# msp_talking_tom_v5.net
KiCad netlist of a schematic drawn in EAGLE
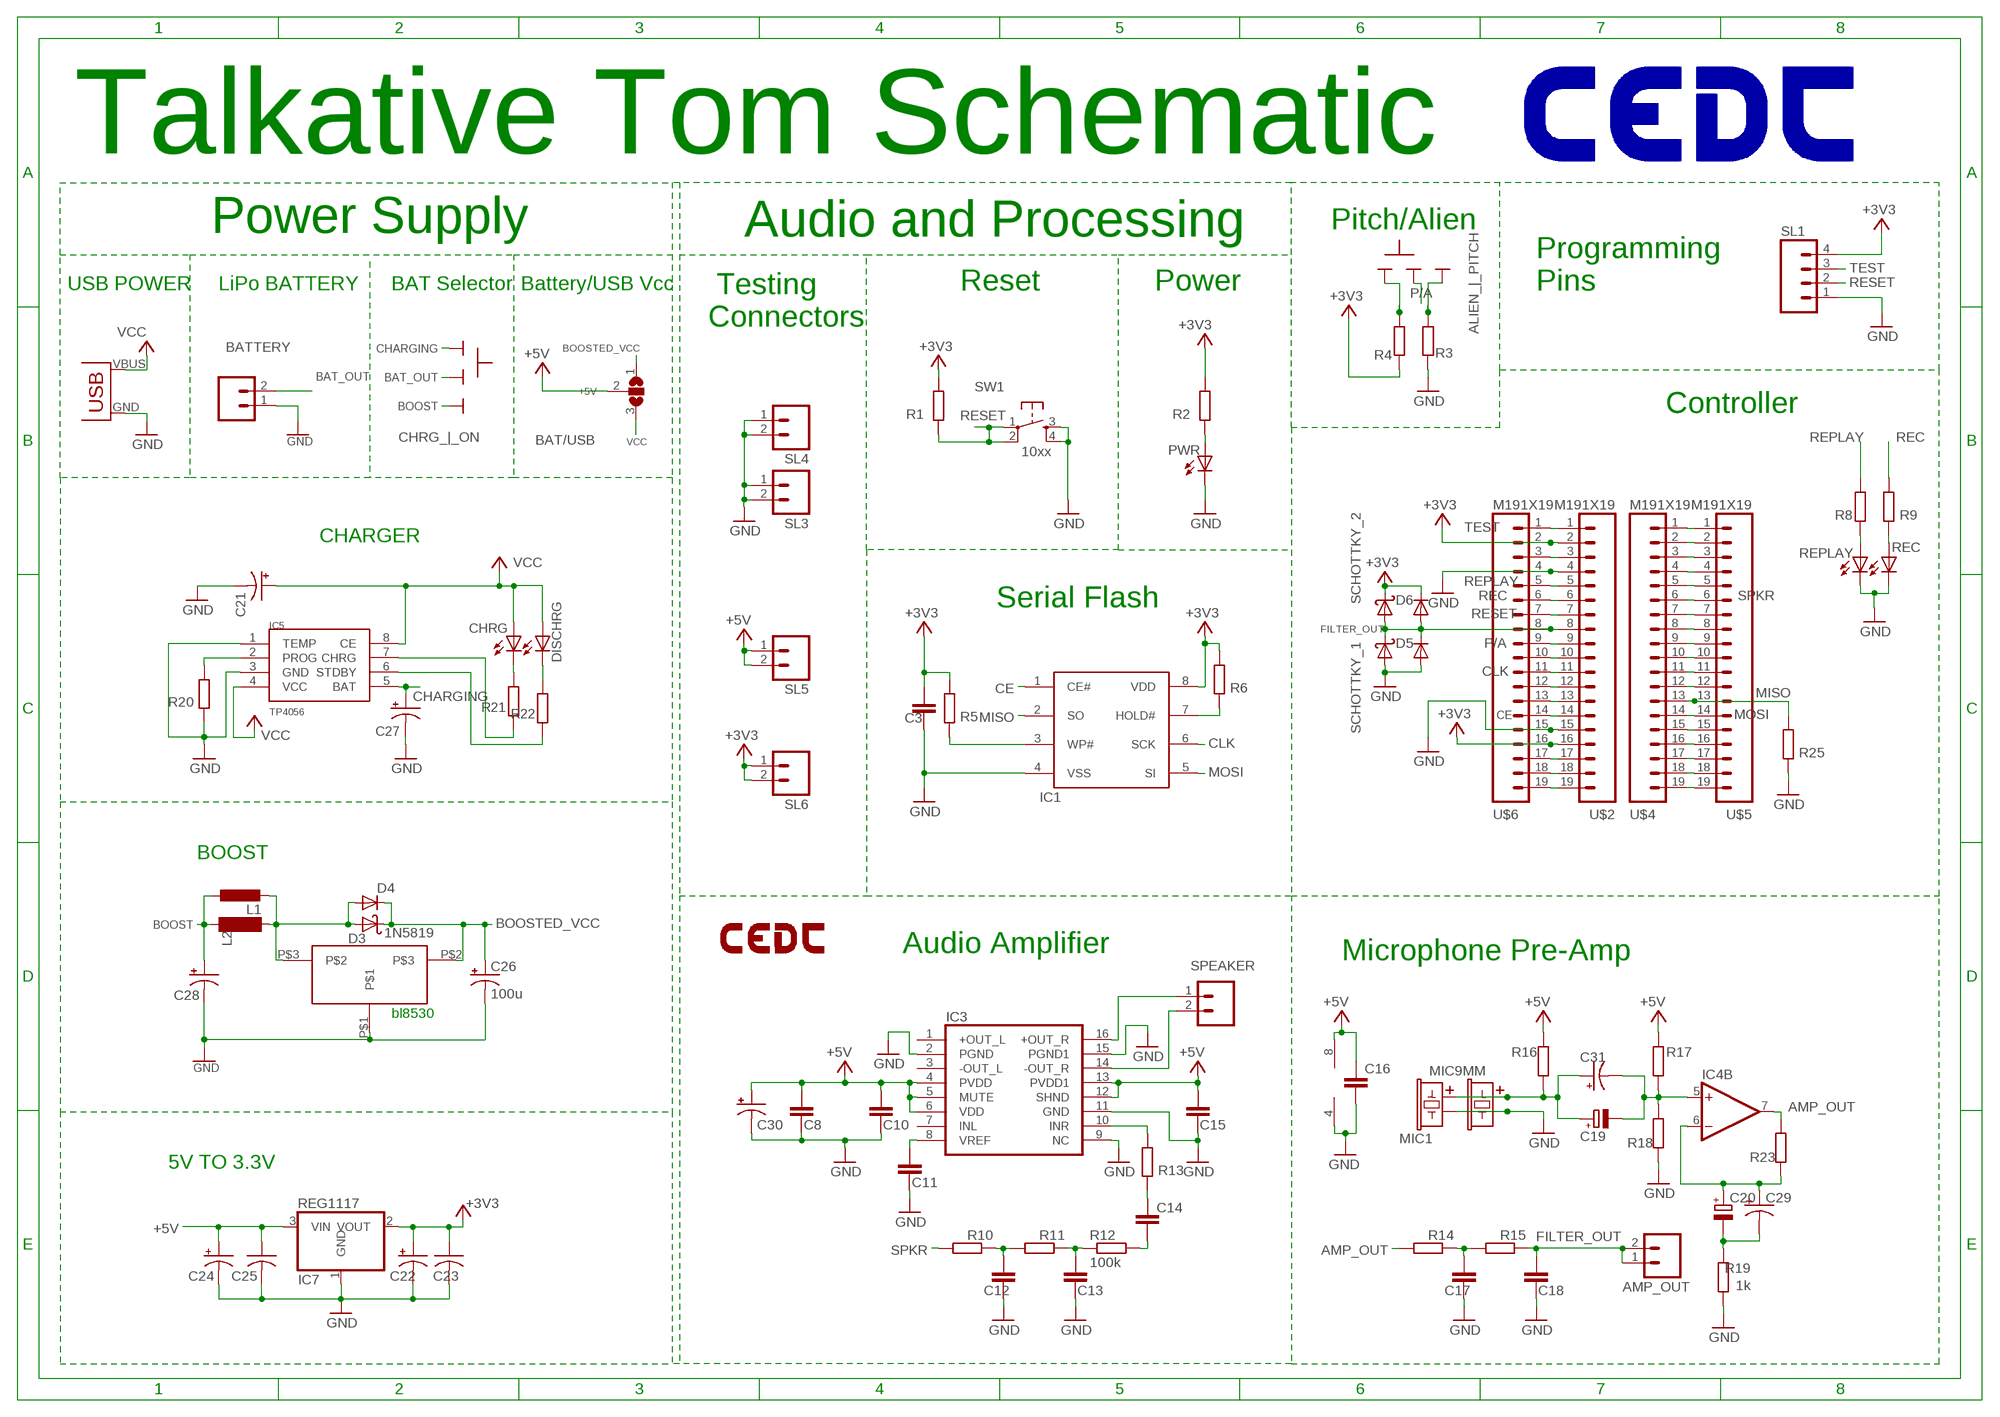
[diagram p0: schematic, sheet 1]

(export (version "E")
  (design (tool "Eeschema 10.0.6"))
  (components
    (comp (ref "ALIEN_|_PITCH")
      (value "SLIDESWITCH-BIG")
      (footprint "eagle-import:BIGSWITCH")
      (libsource (lib "eagle-import") (part "SLIDESWITCH-BIG"))
    )
    (comp (ref "AMP_OUT")
      (value "M02")
      (footprint "eagle-import:02P")
      (libsource (lib "eagle-import") (part "M02"))
    )
    (comp (ref "BAT/USB")
      (value "SJ2W")
      (footprint "eagle-import:SJ_2")
      (libsource (lib "eagle-import") (part "SJ2W"))
    )
    (comp (ref "BATTERY")
      (value "M02JST-PTH-2")
      (footprint "eagle-import:02P")
      (libsource (lib "eagle-import") (part "M02"))
    )
    (comp (ref "C3")
      (value "0.1u")
      (footprint "eagle-import:C0805")
      (libsource (lib "eagle-import") (part "rcl_C-EUC0805"))
    )
    (comp (ref "C8")
      (value "1uf")
      (footprint "eagle-import:C1206")
      (libsource (lib "eagle-import") (part "rcl_C-EUC1206"))
    )
    (comp (ref "C10")
      (value "1uf")
      (footprint "eagle-import:C1206")
      (libsource (lib "eagle-import") (part "rcl_C-EUC1206"))
    )
    (comp (ref "C11")
      (value "0.1uf")
      (footprint "eagle-import:C1206")
      (libsource (lib "eagle-import") (part "rcl_C-EUC1206"))
    )
    (comp (ref "C12")
      (value "0.1u")
      (footprint "eagle-import:C0805")
      (libsource (lib "eagle-import") (part "C-EUC0805"))
    )
    (comp (ref "C13")
      (value "0.1uf")
      (footprint "eagle-import:C0805")
      (libsource (lib "eagle-import") (part "C-EUC0805"))
    )
    (comp (ref "C14")
      (value "0.47uF")
      (footprint "eagle-import:C0603")
      (libsource (lib "eagle-import") (part "rcl_C-EUC0603"))
    )
    (comp (ref "C15")
      (value "1uf")
      (footprint "eagle-import:C1206")
      (libsource (lib "eagle-import") (part "rcl_C-EUC1206"))
    )
    (comp (ref "C16")
      (value "0.1u")
      (footprint "eagle-import:C0805")
      (libsource (lib "eagle-import") (part "resistor_C-EUC0805"))
    )
    (comp (ref "C17")
      (value "0.1u")
      (footprint "eagle-import:C0805")
      (libsource (lib "eagle-import") (part "C-EUC0805"))
    )
    (comp (ref "C18")
      (value "0.1u")
      (footprint "eagle-import:C0805")
      (libsource (lib "eagle-import") (part "C-EUC0805"))
    )
    (comp (ref "C19")
      (value "10u")
      (footprint "eagle-import:E2,5-5")
      (libsource (lib "eagle-import") (part "CPOL-EUE2.5-5"))
    )
    (comp (ref "C20")
      (value "10u")
      (footprint "eagle-import:E2,5-5")
      (libsource (lib "eagle-import") (part "CPOL-EUE2.5-5"))
    )
    (comp (ref "C21")
      (value "10u")
      (footprint "eagle-import:C_6032-28R")
      (libsource (lib "eagle-import") (part "CEDT_JANUARY_2015_v7_CAP_POL_10V"))
    )
    (comp (ref "C22")
      (value "10u")
      (footprint "eagle-import:C_6032-28R")
      (libsource (lib "eagle-import") (part "CAP_POL_10V"))
    )
    (comp (ref "C23")
      (value "0.1u")
      (footprint "eagle-import:C0805")
      (libsource (lib "eagle-import") (part "CAP0805"))
    )
    (comp (ref "C24")
      (value "10u")
      (footprint "eagle-import:C_6032-28R")
      (libsource (lib "eagle-import") (part "CAP_POL_10V"))
    )
    (comp (ref "C25")
      (value "0.1u")
      (footprint "eagle-import:C0805")
      (libsource (lib "eagle-import") (part "CAP0805"))
    )
    (comp (ref "C26")
      (value "100u")
      (footprint "eagle-import:C_6032-28R")
      (libsource (lib "eagle-import") (part "CEDT_JANUARY_2015_v7_CAP_POL_10V"))
    )
    (comp (ref "C27")
      (value "10u")
      (footprint "eagle-import:C_6032-28R")
      (libsource (lib "eagle-import") (part "CAP_POL_10V"))
    )
    (comp (ref "C28")
      (value "10u")
      (footprint "eagle-import:C_6032-28R")
      (libsource (lib "eagle-import") (part "CAP_POL_10V"))
    )
    (comp (ref "C29")
      (value "10u")
      (footprint "eagle-import:C_6032-28R")
      (libsource (lib "eagle-import") (part "CEDT_JANUARY_2015_v7_CAP_POL_10V"))
    )
    (comp (ref "C30")
      (value "CAP_POL_10V")
      (footprint "eagle-import:C_6032-28R")
      (libsource (lib "eagle-import") (part "CEDT_SEPTEMBER_V2_CAP_POL_10V"))
    )
    (comp (ref "C31")
      (value "10u")
      (footprint "eagle-import:C_6032-28R")
      (libsource (lib "eagle-import") (part "CEDT_JANUARY_2015_v7_CAP_POL_10V"))
    )
    (comp (ref "CHRG")
      (value "LED3MM")
      (footprint "eagle-import:LED3MM")
      (libsource (lib "eagle-import") (part "adafruit_LED3MM"))
    )
    (comp (ref "CHRG_|_ON")
      (value "SLIDESWITCH-BIG")
      (footprint "eagle-import:BIGSWITCH")
      (libsource (lib "eagle-import") (part "SLIDESWITCH-BIG"))
    )
    (comp (ref "D3")
      (value "1N5819")
      (footprint "eagle-import:DO41-10")
      (libsource (lib "eagle-import") (part "arduinodaya_v9_1N5819"))
    )
    (comp (ref "D4")
      (value "DIODE_DIODE-DO214AC")
      (footprint "eagle-import:DIODE_DO214AC")
      (libsource (lib "eagle-import") (part "DIODE_DIODE-DO214AC"))
    )
    (comp (ref "D5")
      (value "DIODE_DIODE-DO214AC")
      (footprint "eagle-import:DIODE_DO214AC")
      (libsource (lib "eagle-import") (part "DIODE_DIODE-DO214AC"))
    )
    (comp (ref "D6")
      (value "DIODE_DIODE-DO214AC")
      (footprint "eagle-import:DIODE_DO214AC")
      (libsource (lib "eagle-import") (part "DIODE_DIODE-DO214AC"))
    )
    (comp (ref "DISCHRG")
      (value "LED3MM")
      (footprint "eagle-import:LED3MM")
      (libsource (lib "eagle-import") (part "adafruit_LED3MM"))
    )
    (comp (ref "IC1")
      (value "SST25VF040B_SPI_FLASH")
      (footprint "eagle-import:SOIC08")
      (libsource (lib "eagle-import") (part "SST25VF040B_SPI_FLASH"))
    )
    (comp (ref "IC3")
      (value "PAM8403")
      (footprint "eagle-import:SOP-16")
      (libsource (lib "eagle-import") (part "PAM8403"))
    )
    (comp (ref "IC4")
      (value "LM358N")
      (footprint "eagle-import:DIL08")
      (libsource (lib "eagle-import") (part "LM358N"))
    )
    (comp (ref "IC5")
      (value "TP4056")
      (footprint "eagle-import:SOP-8")
      (libsource (lib "eagle-import") (part "TP4056"))
    )
    (comp (ref "IC6")
      (value "BL8530_5V")
      (footprint "eagle-import:BL8530_5V")
      (libsource (lib "eagle-import") (part "BL8530_5V"))
    )
    (comp (ref "IC7")
      (value "REG1117")
      (footprint "eagle-import:SOT223")
      (libsource (lib "eagle-import") (part "REG1117"))
    )
    (comp (ref "L1")
      (value "L-EUL5650M")
      (footprint "eagle-import:L5650M")
      (libsource (lib "eagle-import") (part "L-EUL5650M"))
    )
    (comp (ref "L2")
      (value "47uH")
      (footprint "eagle-import:MS85")
      (libsource (lib "eagle-import") (part "MS85"))
    )
    (comp (ref "LOGO2")
      (value "LOGO-CEDTSILK-18MM")
      (footprint "eagle-import:LOGO-CEDT-SILK-18MM")
      (libsource (lib "eagle-import") (part "LOGO-CEDTSILK-18MM"))
    )
    (comp (ref "MIC1")
      (value "MICMIC-4.5MM")
      (footprint "eagle-import:MIC-4.5MM")
      (libsource (lib "eagle-import") (part "MICMIC-4.5MM"))
    )
    (comp (ref "MIC9MM")
      (value "MIC9.7MM")
      (footprint "eagle-import:MIC-9.7MM")
      (libsource (lib "eagle-import") (part "MIC9.7MM"))
    )
    (comp (ref "PWR")
      (value "LED3MM")
      (footprint "eagle-import:LED3MM")
      (libsource (lib "eagle-import") (part "LED3MM"))
    )
    (comp (ref "R1")
      (value "10k")
      (footprint "eagle-import:0204_7")
      (libsource (lib "eagle-import") (part "R-EU_0204/7"))
    )
    (comp (ref "R2")
      (value "1k")
      (footprint "eagle-import:0204_7")
      (libsource (lib "eagle-import") (part "R-EU_0204/7"))
    )
    (comp (ref "R3")
      (value "10k")
      (footprint "eagle-import:0204_7")
      (libsource (lib "eagle-import") (part "R-EU_0204/7"))
    )
    (comp (ref "R4")
      (value "10k")
      (footprint "eagle-import:0204_7")
      (libsource (lib "eagle-import") (part "R-EU_0204/7"))
    )
    (comp (ref "R5")
      (value "10k")
      (footprint "eagle-import:0204_7")
      (libsource (lib "eagle-import") (part "R-EU_0204/7"))
    )
    (comp (ref "R6")
      (value "10k")
      (footprint "eagle-import:0204_7")
      (libsource (lib "eagle-import") (part "R-EU_0204/7"))
    )
    (comp (ref "R8")
      (value "1k")
      (footprint "eagle-import:0204_7")
      (libsource (lib "eagle-import") (part "R-EU_0204/7"))
    )
    (comp (ref "R9")
      (value "1k")
      (footprint "eagle-import:0204_7")
      (libsource (lib "eagle-import") (part "R-EU_0204/7"))
    )
    (comp (ref "R10")
      (value "330")
      (footprint "eagle-import:0204_7")
      (libsource (lib "eagle-import") (part "R-EU_0204/7"))
    )
    (comp (ref "R11")
      (value "330")
      (footprint "eagle-import:0204_7")
      (libsource (lib "eagle-import") (part "R-EU_0204/7"))
    )
    (comp (ref "R12")
      (value "100k")
      (footprint "eagle-import:0204_7")
      (libsource (lib "eagle-import") (part "resistor_R-EU_0204/7"))
    )
    (comp (ref "R13")
      (value "10k")
      (footprint "eagle-import:0204_7")
      (libsource (lib "eagle-import") (part "resistor_R-EU_0204/7"))
    )
    (comp (ref "R14")
      (value "330")
      (footprint "eagle-import:0204_7")
      (libsource (lib "eagle-import") (part "R-EU_0204/7"))
    )
    (comp (ref "R15")
      (value "330")
      (footprint "eagle-import:0204_7")
      (libsource (lib "eagle-import") (part "R-EU_0204/7"))
    )
    (comp (ref "R16")
      (value "4.7k")
      (footprint "eagle-import:0204_7")
      (libsource (lib "eagle-import") (part "resistor_R-EU_0204/7"))
    )
    (comp (ref "R17")
      (value "20k")
      (footprint "eagle-import:0204_7")
      (libsource (lib "eagle-import") (part "resistor_R-EU_0204/7"))
    )
    (comp (ref "R18")
      (value "10k")
      (footprint "eagle-import:0204_7")
      (libsource (lib "eagle-import") (part "R-EU_0204/7"))
    )
    (comp (ref "R19")
      (value "1k")
      (footprint "eagle-import:0204_7")
      (libsource (lib "eagle-import") (part "resistor_R-EU_0204/7"))
    )
    (comp (ref "R20")
      (value "R-EU_0204/7")
      (footprint "eagle-import:0204_7")
      (libsource (lib "eagle-import") (part "R-EU_0204/7"))
    )
    (comp (ref "R21")
      (value "470")
      (footprint "eagle-import:0204_7")
      (libsource (lib "eagle-import") (part "R-EU_0204/7"))
    )
    (comp (ref "R22")
      (value "470")
      (footprint "eagle-import:0204_7")
      (libsource (lib "eagle-import") (part "R-EU_0204/7"))
    )
    (comp (ref "R23")
      (value "20k")
      (footprint "eagle-import:0204_7")
      (libsource (lib "eagle-import") (part "R-EU_0204/7"))
    )
    (comp (ref "R25")
      (value "10k")
      (footprint "eagle-import:0204_7")
      (libsource (lib "eagle-import") (part "R-EU_0204/7"))
    )
    (comp (ref "REC")
      (value "LED3MM")
      (footprint "eagle-import:LED3MM")
      (libsource (lib "eagle-import") (part "LED3MM"))
    )
    (comp (ref "REPLAY")
      (value "LED3MM")
      (footprint "eagle-import:LED3MM")
      (libsource (lib "eagle-import") (part "LED3MM"))
    )
    (comp (ref "SCHOTTKY_1")
      (value "1N5819")
      (footprint "eagle-import:DO41-10")
      (libsource (lib "eagle-import") (part "1N5819"))
    )
    (comp (ref "SCHOTTKY_2")
      (value "1N5819")
      (footprint "eagle-import:DO41-10")
      (libsource (lib "eagle-import") (part "1N5819"))
    )
    (comp (ref "SL1")
      (value "M04")
      (footprint "eagle-import:04P")
      (libsource (lib "eagle-import") (part "M04"))
    )
    (comp (ref "SL3")
      (value "M02")
      (footprint "eagle-import:02P")
      (libsource (lib "eagle-import") (part "CEDT_JANUARY_2015_v7_M02"))
    )
    (comp (ref "SL4")
      (value "M02")
      (footprint "eagle-import:02P")
      (libsource (lib "eagle-import") (part "CEDT_JANUARY_2015_v7_M02"))
    )
    (comp (ref "SL5")
      (value "M02")
      (footprint "eagle-import:02P")
      (libsource (lib "eagle-import") (part "CEDT_JANUARY_2015_v7_M02"))
    )
    (comp (ref "SL6")
      (value "M02")
      (footprint "eagle-import:02P")
      (libsource (lib "eagle-import") (part "CEDT_JANUARY_2015_v7_M02"))
    )
    (comp (ref "SPEAKER")
      (value "M02JST-PTH-VERT")
      (footprint "eagle-import:02P")
      (libsource (lib "eagle-import") (part "M02"))
    )
    (comp (ref "SW1")
      (value "10xx")
      (footprint "eagle-import:B3F-10XX")
      (libsource (lib "eagle-import") (part "OMRON_SWITCH_10-XX"))
    )
    (comp (ref "U$1")
      (value "USB(POWER)")
      (footprint "eagle-import:USB(POWER)")
      (libsource (lib "eagle-import") (part "USB(POWER)"))
    )
    (comp (ref "U$2")
      (value "M191X19")
      (footprint "eagle-import:1X19")
      (libsource (lib "eagle-import") (part "M191X19"))
    )
    (comp (ref "U$4")
      (value "M191X19")
      (footprint "eagle-import:1X19")
      (libsource (lib "eagle-import") (part "M191X19"))
    )
    (comp (ref "U$5")
      (value "M191X19")
      (footprint "eagle-import:1X19")
      (libsource (lib "eagle-import") (part "M191X19"))
    )
    (comp (ref "U$6")
      (value "M191X19")
      (footprint "eagle-import:1X19")
      (libsource (lib "eagle-import") (part "M191X19"))
    )
  )
  (nets
    (net (code "1") (name "+3V3") (class "Default")
      (node (ref "C22") (pin "+") (pinfunction "+_+") (pintype "passive"))
      (node (ref "C23") (pin "1") (pinfunction "1_1") (pintype "passive"))
      (node (ref "C3") (pin "1") (pinfunction "1_1") (pintype "passive"))
      (node (ref "D6") (pin "C") (pinfunction "C_C") (pintype "passive"))
      (node (ref "IC1") (pin "8") (pinfunction "VDD_8") (pintype "passive"))
      (node (ref "IC7") (pin "2") (pinfunction "VOUT_2") (pintype "output"))
      (node (ref "R1") (pin "2") (pinfunction "2_2") (pintype "passive"))
      (node (ref "R2") (pin "2") (pinfunction "2_2") (pintype "passive"))
      (node (ref "R4") (pin "2") (pinfunction "2_2") (pintype "passive"))
      (node (ref "R5") (pin "1") (pinfunction "1_1") (pintype "passive"))
      (node (ref "R6") (pin "2") (pinfunction "2_2") (pintype "passive"))
      (node (ref "SCHOTTKY_2") (pin "C") (pinfunction "C_C") (pintype "passive"))
      (node (ref "SL1") (pin "4") (pinfunction "4_4") (pintype "passive"))
      (node (ref "SL6") (pin "1") (pinfunction "1_1") (pintype "passive"))
      (node (ref "SL6") (pin "2") (pinfunction "2_2") (pintype "passive"))
      (node (ref "U$2") (pin "16") (pinfunction "16_16") (pintype "passive"))
      (node (ref "U$2") (pin "2") (pinfunction "2_2") (pintype "passive"))
      (node (ref "U$6") (pin "16") (pinfunction "16_16") (pintype "passive"))
      (node (ref "U$6") (pin "2") (pinfunction "2_2") (pintype "passive"))
    )
    (net (code "2") (name "+5V") (class "Default")
      (node (ref "BAT/USB") (pin "2") (pinfunction "2_2") (pintype "passive"))
      (node (ref "C10") (pin "2") (pinfunction "2_2") (pintype "passive"))
      (node (ref "C15") (pin "2") (pinfunction "2_2") (pintype "passive"))
      (node (ref "C16") (pin "1") (pinfunction "1_1") (pintype "passive"))
      (node (ref "C24") (pin "+") (pinfunction "+_+") (pintype "passive"))
      (node (ref "C25") (pin "1") (pinfunction "1_1") (pintype "passive"))
      (node (ref "C30") (pin "+") (pinfunction "+_+") (pintype "passive"))
      (node (ref "C8") (pin "1") (pinfunction "1_1") (pintype "passive"))
      (node (ref "IC3") (pin "12") (pinfunction "SHND_12") (pintype "output"))
      (node (ref "IC3") (pin "13") (pinfunction "PVDD1_13") (pintype "output"))
      (node (ref "IC3") (pin "4") (pinfunction "PVDD_4") (pintype "input"))
      (node (ref "IC3") (pin "5") (pinfunction "MUTE_5") (pintype "input"))
      (node (ref "IC3") (pin "6") (pinfunction "VDD_6") (pintype "input"))
      (node (ref "IC4") (pin "8") (pinfunction "V+_8") (pintype "power_in"))
      (node (ref "IC7") (pin "3") (pinfunction "VIN_3") (pintype "input"))
      (node (ref "R16") (pin "2") (pinfunction "2_2") (pintype "passive"))
      (node (ref "R17") (pin "2") (pinfunction "2_2") (pintype "passive"))
      (node (ref "SL5") (pin "1") (pinfunction "1_1") (pintype "passive"))
      (node (ref "SL5") (pin "2") (pinfunction "2_2") (pintype "passive"))
    )
    (net (code "3") (name "/AMP_OUT") (class "Default")
      (node (ref "IC4") (pin "7") (pinfunction "OUT_7") (pintype "output"))
      (node (ref "R14") (pin "1") (pinfunction "1_1") (pintype "passive"))
      (node (ref "R23") (pin "2") (pinfunction "2_2") (pintype "passive"))
    )
    (net (code "4") (name "/BAT_OUT") (class "Default")
      (node (ref "BATTERY") (pin "2") (pinfunction "2_2") (pintype "passive"))
      (node (ref "CHRG_|_ON") (pin "2") (pinfunction "2_2") (pintype "bidirectional"))
    )
    (net (code "5") (name "/BOOST") (class "Default")
      (node (ref "C28") (pin "+") (pinfunction "+_+") (pintype "passive"))
      (node (ref "CHRG_|_ON") (pin "3") (pinfunction "3_3") (pintype "bidirectional"))
      (node (ref "L1") (pin "1") (pinfunction "1_1") (pintype "passive"))
      (node (ref "L2") (pin "1") (pinfunction "1_1") (pintype "passive"))
    )
    (net (code "6") (name "/BOOSTED_VCC") (class "Default")
      (node (ref "BAT/USB") (pin "1") (pinfunction "1_1") (pintype "passive"))
      (node (ref "C26") (pin "+") (pinfunction "+_+") (pintype "passive"))
      (node (ref "D3") (pin "C") (pinfunction "C_C") (pintype "passive"))
      (node (ref "D4") (pin "C") (pinfunction "C_C") (pintype "passive"))
      (node (ref "IC6") (pin "P$2") (pinfunction "P$3_P$2") (pintype "bidirectional"))
    )
    (net (code "7") (name "/CE") (class "Default")
      (node (ref "IC1") (pin "1") (pinfunction "CE#_1") (pintype "passive"))
      (node (ref "U$2") (pin "14") (pinfunction "14_14") (pintype "passive"))
      (node (ref "U$6") (pin "14") (pinfunction "14_14") (pintype "passive"))
    )
    (net (code "8") (name "/CHARGING") (class "Default")
      (node (ref "C27") (pin "+") (pinfunction "+_+") (pintype "passive"))
      (node (ref "CHRG_|_ON") (pin "1") (pinfunction "1_1") (pintype "bidirectional"))
      (node (ref "IC5") (pin "5") (pinfunction "BAT_5") (pintype "bidirectional"))
    )
    (net (code "9") (name "/CLK") (class "Default")
      (node (ref "IC1") (pin "6") (pinfunction "SCK_6") (pintype "passive"))
      (node (ref "U$2") (pin "11") (pinfunction "11_11") (pintype "passive"))
      (node (ref "U$6") (pin "11") (pinfunction "11_11") (pintype "passive"))
    )
    (net (code "10") (name "/FILTER_OUT") (class "Default")
      (node (ref "AMP_OUT") (pin "1") (pinfunction "1_1") (pintype "passive"))
      (node (ref "AMP_OUT") (pin "2") (pinfunction "2_2") (pintype "passive"))
      (node (ref "C18") (pin "1") (pinfunction "1_1") (pintype "passive"))
      (node (ref "D5") (pin "C") (pinfunction "C_C") (pintype "passive"))
      (node (ref "D6") (pin "A") (pinfunction "A_A") (pintype "passive"))
      (node (ref "R15") (pin "2") (pinfunction "2_2") (pintype "passive"))
      (node (ref "SCHOTTKY_1") (pin "C") (pinfunction "C_C") (pintype "passive"))
      (node (ref "SCHOTTKY_2") (pin "A") (pinfunction "A_A") (pintype "passive"))
      (node (ref "U$2") (pin "8") (pinfunction "8_8") (pintype "passive"))
      (node (ref "U$6") (pin "8") (pinfunction "8_8") (pintype "passive"))
    )
    (net (code "11") (name "/MISO") (class "Default")
      (node (ref "IC1") (pin "2") (pinfunction "SO_2") (pintype "passive"))
      (node (ref "R25") (pin "2") (pinfunction "2_2") (pintype "passive"))
      (node (ref "U$4") (pin "13") (pinfunction "13_13") (pintype "passive"))
      (node (ref "U$5") (pin "13") (pinfunction "13_13") (pintype "passive"))
    )
    (net (code "12") (name "/MOSI") (class "Default")
      (node (ref "IC1") (pin "5") (pinfunction "SI_5") (pintype "passive"))
      (node (ref "U$4") (pin "14") (pinfunction "14_14") (pintype "passive"))
      (node (ref "U$5") (pin "14") (pinfunction "14_14") (pintype "passive"))
    )
    (net (code "13") (name "/P{slash}A") (class "Default")
      (node (ref "ALIEN_|_PITCH") (pin "2") (pinfunction "2_2") (pintype "bidirectional"))
      (node (ref "U$2") (pin "9") (pinfunction "9_9") (pintype "passive"))
      (node (ref "U$6") (pin "9") (pinfunction "9_9") (pintype "passive"))
    )
    (net (code "14") (name "/REC") (class "Default")
      (node (ref "R9") (pin "1") (pinfunction "1_1") (pintype "passive"))
      (node (ref "U$2") (pin "6") (pinfunction "6_6") (pintype "passive"))
      (node (ref "U$6") (pin "6") (pinfunction "6_6") (pintype "passive"))
    )
    (net (code "15") (name "/REPLAY") (class "Default")
      (node (ref "R8") (pin "2") (pinfunction "2_2") (pintype "passive"))
      (node (ref "U$2") (pin "5") (pinfunction "5_5") (pintype "passive"))
      (node (ref "U$6") (pin "5") (pinfunction "5_5") (pintype "passive"))
    )
    (net (code "16") (name "/RESET") (class "Default")
      (node (ref "R1") (pin "1") (pinfunction "1_1") (pintype "passive"))
      (node (ref "SL1") (pin "2") (pinfunction "2_2") (pintype "passive"))
      (node (ref "SW1") (pin "1") (pinfunction "P_1") (pintype "passive"))
      (node (ref "SW1") (pin "2") (pinfunction "P1_2") (pintype "passive"))
      (node (ref "U$2") (pin "7") (pinfunction "7_7") (pintype "passive"))
      (node (ref "U$6") (pin "7") (pinfunction "7_7") (pintype "passive"))
    )
    (net (code "17") (name "/SPKR") (class "Default")
      (node (ref "R10") (pin "1") (pinfunction "1_1") (pintype "passive"))
      (node (ref "U$4") (pin "6") (pinfunction "6_6") (pintype "passive"))
      (node (ref "U$5") (pin "6") (pinfunction "6_6") (pintype "passive"))
    )
    (net (code "18") (name "/TEST") (class "Default")
      (node (ref "SL1") (pin "3") (pinfunction "3_3") (pintype "passive"))
      (node (ref "U$2") (pin "1") (pinfunction "1_1") (pintype "passive"))
      (node (ref "U$6") (pin "1") (pinfunction "1_1") (pintype "passive"))
    )
    (net (code "19") (name "GND") (class "Default")
      (node (ref "BATTERY") (pin "1") (pinfunction "1_1") (pintype "passive"))
      (node (ref "C10") (pin "1") (pinfunction "1_1") (pintype "passive"))
      (node (ref "C11") (pin "2") (pinfunction "2_2") (pintype "passive"))
      (node (ref "C12") (pin "2") (pinfunction "2_2") (pintype "passive"))
      (node (ref "C13") (pin "2") (pinfunction "2_2") (pintype "passive"))
      (node (ref "C15") (pin "1") (pinfunction "1_1") (pintype "passive"))
      (node (ref "C16") (pin "2") (pinfunction "2_2") (pintype "passive"))
      (node (ref "C17") (pin "2") (pinfunction "2_2") (pintype "passive"))
      (node (ref "C18") (pin "2") (pinfunction "2_2") (pintype "passive"))
      (node (ref "C21") (pin "-") (pinfunction "-_-") (pintype "passive"))
      (node (ref "C22") (pin "-") (pinfunction "-_-") (pintype "passive"))
      (node (ref "C23") (pin "2") (pinfunction "2_2") (pintype "passive"))
      (node (ref "C24") (pin "-") (pinfunction "-_-") (pintype "passive"))
      (node (ref "C25") (pin "2") (pinfunction "2_2") (pintype "passive"))
      (node (ref "C26") (pin "-") (pinfunction "-_-") (pintype "passive"))
      (node (ref "C27") (pin "-") (pinfunction "-_-") (pintype "passive"))
      (node (ref "C28") (pin "-") (pinfunction "-_-") (pintype "passive"))
      (node (ref "C3") (pin "2") (pinfunction "2_2") (pintype "passive"))
      (node (ref "C30") (pin "-") (pinfunction "-_-") (pintype "passive"))
      (node (ref "C8") (pin "2") (pinfunction "2_2") (pintype "passive"))
      (node (ref "D5") (pin "A") (pinfunction "A_A") (pintype "passive"))
      (node (ref "IC1") (pin "4") (pinfunction "VSS_4") (pintype "passive"))
      (node (ref "IC3") (pin "11") (pinfunction "GND_11") (pintype "output"))
      (node (ref "IC3") (pin "15") (pinfunction "PGND1_15") (pintype "output"))
      (node (ref "IC3") (pin "2") (pinfunction "PGND_2") (pintype "input"))
      (node (ref "IC3") (pin "9") (pinfunction "NC_9") (pintype "output"))
      (node (ref "IC4") (pin "4") (pinfunction "V-_4") (pintype "power_in"))
      (node (ref "IC5") (pin "1") (pinfunction "TEMP_1") (pintype "bidirectional"))
      (node (ref "IC5") (pin "3") (pinfunction "GND_3") (pintype "bidirectional"))
      (node (ref "IC6") (pin "P$1") (pinfunction "P$1_P$1") (pintype "bidirectional"))
      (node (ref "IC7") (pin "1") (pinfunction "GND_1") (pintype "power_in"))
      (node (ref "MIC1") (pin "+") (pinfunction "2_+") (pintype "passive"))
      (node (ref "MIC9MM") (pin "2") (pinfunction "2_2") (pintype "passive"))
      (node (ref "PWR") (pin "K") (pinfunction "C_K") (pintype "passive"))
      (node (ref "R18") (pin "1") (pinfunction "1_1") (pintype "passive"))
      (node (ref "R19") (pin "1") (pinfunction "1_1") (pintype "passive"))
      (node (ref "R20") (pin "1") (pinfunction "1_1") (pintype "passive"))
      (node (ref "R25") (pin "1") (pinfunction "1_1") (pintype "passive"))
      (node (ref "R3") (pin "2") (pinfunction "2_2") (pintype "passive"))
      (node (ref "REC") (pin "K") (pinfunction "C_K") (pintype "passive"))
      (node (ref "REPLAY") (pin "K") (pinfunction "C_K") (pintype "passive"))
      (node (ref "SCHOTTKY_1") (pin "A") (pinfunction "A_A") (pintype "passive"))
      (node (ref "SL1") (pin "1") (pinfunction "1_1") (pintype "passive"))
      (node (ref "SL3") (pin "1") (pinfunction "1_1") (pintype "passive"))
      (node (ref "SL3") (pin "2") (pinfunction "2_2") (pintype "passive"))
      (node (ref "SL4") (pin "1") (pinfunction "1_1") (pintype "passive"))
      (node (ref "SL4") (pin "2") (pinfunction "2_2") (pintype "passive"))
      (node (ref "SW1") (pin "3") (pinfunction "S_3") (pintype "passive"))
      (node (ref "SW1") (pin "4") (pinfunction "S1_4") (pintype "passive"))
      (node (ref "U$1") (pin "GND") (pinfunction "GND_GND") (pintype "power_in"))
      (node (ref "U$2") (pin "15") (pinfunction "15_15") (pintype "passive"))
      (node (ref "U$2") (pin "4") (pinfunction "4_4") (pintype "passive"))
      (node (ref "U$6") (pin "15") (pinfunction "15_15") (pintype "passive"))
      (node (ref "U$6") (pin "4") (pinfunction "4_4") (pintype "passive"))
    )
    (net (code "20") (name "Net-(ALIEN_|_PITCH-Pad1)") (class "Default")
      (node (ref "ALIEN_|_PITCH") (pin "1") (pinfunction "1_1") (pintype "bidirectional"))
      (node (ref "R4") (pin "1") (pinfunction "1_1") (pintype "passive"))
    )
    (net (code "21") (name "Net-(ALIEN_|_PITCH-Pad3)") (class "Default")
      (node (ref "ALIEN_|_PITCH") (pin "3") (pinfunction "3_3") (pintype "bidirectional"))
      (node (ref "R3") (pin "1") (pinfunction "1_1") (pintype "passive"))
    )
    (net (code "22") (name "Net-(C12-Pad1)") (class "Default")
      (node (ref "C12") (pin "1") (pinfunction "1_1") (pintype "passive"))
      (node (ref "R10") (pin "2") (pinfunction "2_2") (pintype "passive"))
      (node (ref "R11") (pin "1") (pinfunction "1_1") (pintype "passive"))
    )
    (net (code "23") (name "Net-(C13-Pad1)") (class "Default")
      (node (ref "C13") (pin "1") (pinfunction "1_1") (pintype "passive"))
      (node (ref "R11") (pin "2") (pinfunction "2_2") (pintype "passive"))
      (node (ref "R12") (pin "1") (pinfunction "1_1") (pintype "passive"))
    )
    (net (code "24") (name "Net-(C14-Pad1)") (class "Default")
      (node (ref "C14") (pin "1") (pinfunction "1_1") (pintype "passive"))
      (node (ref "R12") (pin "2") (pinfunction "2_2") (pintype "passive"))
    )
    (net (code "25") (name "Net-(C14-Pad2)") (class "Default")
      (node (ref "C14") (pin "2") (pinfunction "2_2") (pintype "passive"))
      (node (ref "R13") (pin "2") (pinfunction "2_2") (pintype "passive"))
    )
    (net (code "26") (name "Net-(C17-Pad1)") (class "Default")
      (node (ref "C17") (pin "1") (pinfunction "1_1") (pintype "passive"))
      (node (ref "R14") (pin "2") (pinfunction "2_2") (pintype "passive"))
      (node (ref "R15") (pin "1") (pinfunction "1_1") (pintype "passive"))
    )
    (net (code "27") (name "Net-(C20-Pad-)") (class "Default")
      (node (ref "C20") (pin "-") (pinfunction "-_-") (pintype "passive"))
      (node (ref "C29") (pin "-") (pinfunction "-_-") (pintype "passive"))
      (node (ref "R19") (pin "2") (pinfunction "2_2") (pintype "passive"))
    )
    (net (code "28") (name "Net-(CHRG-C)") (class "Default")
      (node (ref "CHRG") (pin "K") (pinfunction "C_K") (pintype "passive"))
      (node (ref "R21") (pin "2") (pinfunction "2_2") (pintype "passive"))
    )
    (net (code "29") (name "Net-(DISCHRG-C)") (class "Default")
      (node (ref "DISCHRG") (pin "K") (pinfunction "C_K") (pintype "passive"))
      (node (ref "R22") (pin "2") (pinfunction "2_2") (pintype "passive"))
    )
    (net (code "30") (name "Net-(IC1-HOLD#)") (class "Default")
      (node (ref "IC1") (pin "7") (pinfunction "HOLD#_7") (pintype "passive"))
      (node (ref "R6") (pin "1") (pinfunction "1_1") (pintype "passive"))
    )
    (net (code "31") (name "Net-(IC1-WP#)") (class "Default")
      (node (ref "IC1") (pin "3") (pinfunction "WP#_3") (pintype "passive"))
      (node (ref "R5") (pin "2") (pinfunction "2_2") (pintype "passive"))
    )
    (net (code "32") (name "Net-(IC3-+OUT_R)") (class "Default")
      (node (ref "IC3") (pin "16") (pinfunction "+OUT_R_16") (pintype "output"))
      (node (ref "SPEAKER") (pin "1") (pinfunction "1_1") (pintype "passive"))
    )
    (net (code "33") (name "Net-(IC3--OUT_R)") (class "Default")
      (node (ref "IC3") (pin "14") (pinfunction "-OUT_R_14") (pintype "output"))
      (node (ref "SPEAKER") (pin "2") (pinfunction "2_2") (pintype "passive"))
    )
    (net (code "34") (name "Net-(IC3-INR)") (class "Default")
      (node (ref "IC3") (pin "10") (pinfunction "INR_10") (pintype "output"))
      (node (ref "R13") (pin "1") (pinfunction "1_1") (pintype "passive"))
    )
    (net (code "35") (name "Net-(IC3-VREF)") (class "Default")
      (node (ref "C11") (pin "1") (pinfunction "1_1") (pintype "passive"))
      (node (ref "IC3") (pin "8") (pinfunction "VREF_8") (pintype "input"))
    )
    (net (code "36") (name "Net-(IC4B-+IN)") (class "Default")
      (node (ref "C19") (pin "-") (pinfunction "-_-") (pintype "passive"))
      (node (ref "C31") (pin "-") (pinfunction "-_-") (pintype "passive"))
      (node (ref "IC4") (pin "5") (pinfunction "+IN_5") (pintype "input"))
      (node (ref "R17") (pin "1") (pinfunction "1_1") (pintype "passive"))
      (node (ref "R18") (pin "2") (pinfunction "2_2") (pintype "passive"))
    )
    (net (code "37") (name "Net-(IC4B--IN)") (class "Default")
      (node (ref "C20") (pin "+") (pinfunction "+_+") (pintype "passive"))
      (node (ref "C29") (pin "+") (pinfunction "+_+") (pintype "passive"))
      (node (ref "IC4") (pin "6") (pinfunction "-IN_6") (pintype "input"))
      (node (ref "R23") (pin "1") (pinfunction "1_1") (pintype "passive"))
    )
    (net (code "38") (name "Net-(IC5-CHRG)") (class "Default")
      (node (ref "IC5") (pin "7") (pinfunction "CHRG_7") (pintype "bidirectional"))
      (node (ref "R21") (pin "1") (pinfunction "1_1") (pintype "passive"))
    )
    (net (code "39") (name "Net-(IC5-PROG)") (class "Default")
      (node (ref "IC5") (pin "2") (pinfunction "PROG_2") (pintype "bidirectional"))
      (node (ref "R20") (pin "2") (pinfunction "2_2") (pintype "passive"))
    )
    (net (code "40") (name "Net-(IC5-STDBY)") (class "Default")
      (node (ref "IC5") (pin "6") (pinfunction "STDBY_6") (pintype "bidirectional"))
      (node (ref "R22") (pin "1") (pinfunction "1_1") (pintype "passive"))
    )
    (net (code "41") (name "Net-(IC6-P$2)") (class "Default")
      (node (ref "D3") (pin "A") (pinfunction "A_A") (pintype "passive"))
      (node (ref "D4") (pin "A") (pinfunction "A_A") (pintype "passive"))
      (node (ref "IC6") (pin "P$3") (pinfunction "P$2_P$3") (pintype "bidirectional"))
      (node (ref "L1") (pin "2") (pinfunction "2_2") (pintype "passive"))
      (node (ref "L2") (pin "2") (pinfunction "2_2") (pintype "passive"))
    )
    (net (code "42") (name "Net-(MIC1-1)") (class "Default")
      (node (ref "C19") (pin "+") (pinfunction "+_+") (pintype "passive"))
      (node (ref "C31") (pin "+") (pinfunction "+_+") (pintype "passive"))
      (node (ref "MIC1") (pin "-") (pinfunction "1_-") (pintype "passive"))
      (node (ref "MIC9MM") (pin "1") (pinfunction "1_1") (pintype "passive"))
      (node (ref "R16") (pin "1") (pinfunction "1_1") (pintype "passive"))
    )
    (net (code "43") (name "Net-(PWR-PadA)") (class "Default")
      (node (ref "PWR") (pin "A") (pinfunction "A_A") (pintype "passive"))
      (node (ref "R2") (pin "1") (pinfunction "1_1") (pintype "passive"))
    )
    (net (code "44") (name "Net-(R8-Pad1)") (class "Default")
      (node (ref "R8") (pin "1") (pinfunction "1_1") (pintype "passive"))
      (node (ref "REPLAY") (pin "A") (pinfunction "A_A") (pintype "passive"))
    )
    (net (code "45") (name "Net-(R9-Pad2)") (class "Default")
      (node (ref "R9") (pin "2") (pinfunction "2_2") (pintype "passive"))
      (node (ref "REC") (pin "A") (pinfunction "A_A") (pintype "passive"))
    )
    (net (code "46") (name "Net-(U$2-Pad3)") (class "Default")
      (node (ref "U$2") (pin "3") (pinfunction "3_3") (pintype "passive"))
      (node (ref "U$6") (pin "3") (pinfunction "3_3") (pintype "passive"))
    )
    (net (code "47") (name "Net-(U$2-Pad10)") (class "Default")
      (node (ref "U$2") (pin "10") (pinfunction "10_10") (pintype "passive"))
      (node (ref "U$6") (pin "10") (pinfunction "10_10") (pintype "passive"))
    )
    (net (code "48") (name "Net-(U$2-Pad12)") (class "Default")
      (node (ref "U$2") (pin "12") (pinfunction "12_12") (pintype "passive"))
      (node (ref "U$6") (pin "12") (pinfunction "12_12") (pintype "passive"))
    )
    (net (code "49") (name "Net-(U$2-Pad13)") (class "Default")
      (node (ref "U$2") (pin "13") (pinfunction "13_13") (pintype "passive"))
      (node (ref "U$6") (pin "13") (pinfunction "13_13") (pintype "passive"))
    )
    (net (code "50") (name "Net-(U$2-Pad17)") (class "Default")
      (node (ref "U$2") (pin "17") (pinfunction "17_17") (pintype "passive"))
      (node (ref "U$6") (pin "17") (pinfunction "17_17") (pintype "passive"))
    )
    (net (code "51") (name "Net-(U$2-Pad18)") (class "Default")
      (node (ref "U$2") (pin "18") (pinfunction "18_18") (pintype "passive"))
      (node (ref "U$6") (pin "18") (pinfunction "18_18") (pintype "passive"))
    )
    (net (code "52") (name "Net-(U$2-Pad19)") (class "Default")
      (node (ref "U$2") (pin "19") (pinfunction "19_19") (pintype "passive"))
      (node (ref "U$6") (pin "19") (pinfunction "19_19") (pintype "passive"))
    )
    (net (code "53") (name "Net-(U$4-Pad1)") (class "Default")
      (node (ref "U$4") (pin "1") (pinfunction "1_1") (pintype "passive"))
      (node (ref "U$5") (pin "1") (pinfunction "1_1") (pintype "passive"))
    )
    (net (code "54") (name "Net-(U$4-Pad2)") (class "Default")
      (node (ref "U$4") (pin "2") (pinfunction "2_2") (pintype "passive"))
      (node (ref "U$5") (pin "2") (pinfunction "2_2") (pintype "passive"))
    )
    (net (code "55") (name "Net-(U$4-Pad3)") (class "Default")
      (node (ref "U$4") (pin "3") (pinfunction "3_3") (pintype "passive"))
      (node (ref "U$5") (pin "3") (pinfunction "3_3") (pintype "passive"))
    )
    (net (code "56") (name "Net-(U$4-Pad4)") (class "Default")
      (node (ref "U$4") (pin "4") (pinfunction "4_4") (pintype "passive"))
      (node (ref "U$5") (pin "4") (pinfunction "4_4") (pintype "passive"))
    )
    (net (code "57") (name "Net-(U$4-Pad5)") (class "Default")
      (node (ref "U$4") (pin "5") (pinfunction "5_5") (pintype "passive"))
      (node (ref "U$5") (pin "5") (pinfunction "5_5") (pintype "passive"))
    )
    (net (code "58") (name "Net-(U$4-Pad7)") (class "Default")
      (node (ref "U$4") (pin "7") (pinfunction "7_7") (pintype "passive"))
      (node (ref "U$5") (pin "7") (pinfunction "7_7") (pintype "passive"))
    )
    (net (code "59") (name "Net-(U$4-Pad8)") (class "Default")
      (node (ref "U$4") (pin "8") (pinfunction "8_8") (pintype "passive"))
      (node (ref "U$5") (pin "8") (pinfunction "8_8") (pintype "passive"))
    )
    (net (code "60") (name "Net-(U$4-Pad9)") (class "Default")
      (node (ref "U$4") (pin "9") (pinfunction "9_9") (pintype "passive"))
      (node (ref "U$5") (pin "9") (pinfunction "9_9") (pintype "passive"))
    )
    (net (code "61") (name "Net-(U$4-Pad10)") (class "Default")
      (node (ref "U$4") (pin "10") (pinfunction "10_10") (pintype "passive"))
      (node (ref "U$5") (pin "10") (pinfunction "10_10") (pintype "passive"))
    )
    (net (code "62") (name "Net-(U$4-Pad11)") (class "Default")
      (node (ref "U$4") (pin "11") (pinfunction "11_11") (pintype "passive"))
      (node (ref "U$5") (pin "11") (pinfunction "11_11") (pintype "passive"))
    )
    (net (code "63") (name "Net-(U$4-Pad12)") (class "Default")
      (node (ref "U$4") (pin "12") (pinfunction "12_12") (pintype "passive"))
      (node (ref "U$5") (pin "12") (pinfunction "12_12") (pintype "passive"))
    )
    (net (code "64") (name "Net-(U$4-Pad15)") (class "Default")
      (node (ref "U$4") (pin "15") (pinfunction "15_15") (pintype "passive"))
      (node (ref "U$5") (pin "15") (pinfunction "15_15") (pintype "passive"))
    )
    (net (code "65") (name "Net-(U$4-Pad16)") (class "Default")
      (node (ref "U$4") (pin "16") (pinfunction "16_16") (pintype "passive"))
      (node (ref "U$5") (pin "16") (pinfunction "16_16") (pintype "passive"))
    )
    (net (code "66") (name "Net-(U$4-Pad17)") (class "Default")
      (node (ref "U$4") (pin "17") (pinfunction "17_17") (pintype "passive"))
      (node (ref "U$5") (pin "17") (pinfunction "17_17") (pintype "passive"))
    )
    (net (code "67") (name "Net-(U$4-Pad18)") (class "Default")
      (node (ref "U$4") (pin "18") (pinfunction "18_18") (pintype "passive"))
      (node (ref "U$5") (pin "18") (pinfunction "18_18") (pintype "passive"))
    )
    (net (code "68") (name "Net-(U$4-Pad19)") (class "Default")
      (node (ref "U$4") (pin "19") (pinfunction "19_19") (pintype "passive"))
      (node (ref "U$5") (pin "19") (pinfunction "19_19") (pintype "passive"))
    )
    (net (code "69") (name "VCC") (class "Default")
      (node (ref "BAT/USB") (pin "3") (pinfunction "3_3") (pintype "passive"))
      (node (ref "C21") (pin "+") (pinfunction "+_+") (pintype "passive"))
      (node (ref "CHRG") (pin "A") (pinfunction "A_A") (pintype "passive"))
      (node (ref "DISCHRG") (pin "A") (pinfunction "A_A") (pintype "passive"))
      (node (ref "IC5") (pin "4") (pinfunction "VCC_4") (pintype "bidirectional"))
      (node (ref "IC5") (pin "8") (pinfunction "CE_8") (pintype "bidirectional"))
      (node (ref "U$1") (pin "VBUS") (pinfunction "VCC_VBUS") (pintype "power_in"))
    )
    (net (code "70") (name "unconnected-(IC3-+OUT_L-Pad1)") (class "Default")
      (node (ref "IC3") (pin "1") (pinfunction "+OUT_L_1") (pintype "input"))
    )
    (net (code "71") (name "unconnected-(IC3--OUT_L-Pad3)") (class "Default")
      (node (ref "IC3") (pin "3") (pinfunction "-OUT_L_3") (pintype "input"))
    )
    (net (code "72") (name "unconnected-(IC3-INL-Pad7)") (class "Default")
      (node (ref "IC3") (pin "7") (pinfunction "INL_7") (pintype "input"))
    )
  )
)
